# seven_segment_all.net
KiCad netlist of a schematic drawn in EAGLE
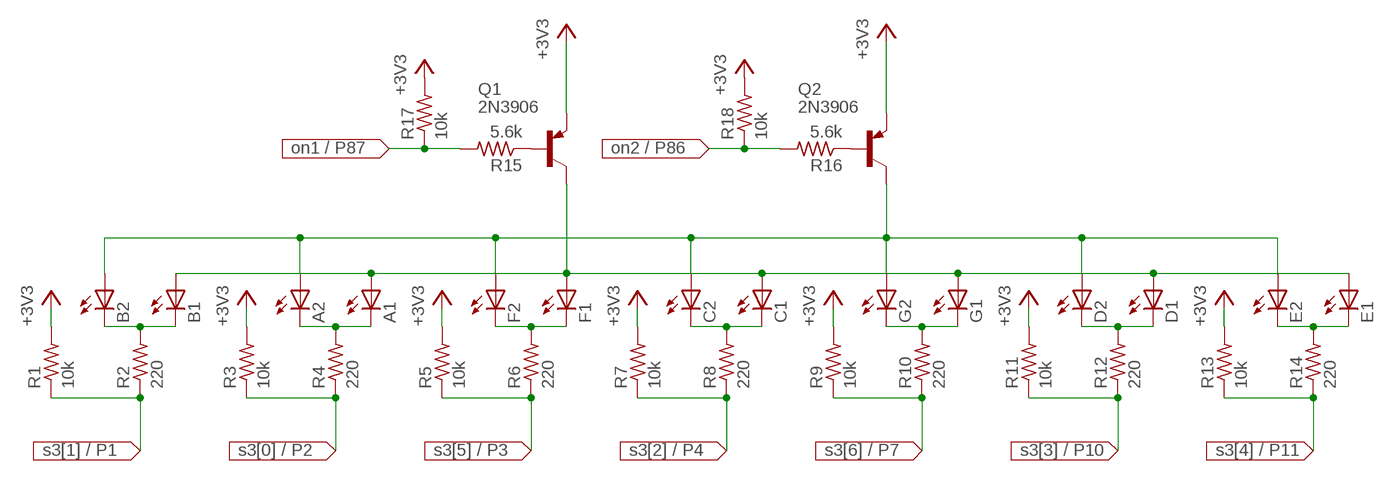
[diagram p0: schematic, sheet 1]

(export (version "E")
  (design (tool "Eeschema 10.0.6"))
  (components
    (comp (ref "A1")
      (value "LED5MM")
      (footprint "eagle-import:LED5MM")
      (libsource (lib "eagle-import") (part "LED5MM"))
    )
    (comp (ref "A2")
      (value "LED5MM")
      (footprint "eagle-import:LED5MM")
      (libsource (lib "eagle-import") (part "LED5MM"))
    )
    (comp (ref "B1")
      (value "LED5MM")
      (footprint "eagle-import:LED5MM")
      (libsource (lib "eagle-import") (part "LED5MM"))
    )
    (comp (ref "B2")
      (value "LED5MM")
      (footprint "eagle-import:LED5MM")
      (libsource (lib "eagle-import") (part "LED5MM"))
    )
    (comp (ref "C1")
      (value "LED5MM")
      (footprint "eagle-import:LED5MM")
      (libsource (lib "eagle-import") (part "LED5MM"))
    )
    (comp (ref "C2")
      (value "LED5MM")
      (footprint "eagle-import:LED5MM")
      (libsource (lib "eagle-import") (part "LED5MM"))
    )
    (comp (ref "D1")
      (value "LED5MM")
      (footprint "eagle-import:LED5MM")
      (libsource (lib "eagle-import") (part "LED5MM"))
    )
    (comp (ref "D2")
      (value "LED5MM")
      (footprint "eagle-import:LED5MM")
      (libsource (lib "eagle-import") (part "LED5MM"))
    )
    (comp (ref "E1")
      (value "LED5MM")
      (footprint "eagle-import:LED5MM")
      (libsource (lib "eagle-import") (part "LED5MM"))
    )
    (comp (ref "E2")
      (value "LED5MM")
      (footprint "eagle-import:LED5MM")
      (libsource (lib "eagle-import") (part "LED5MM"))
    )
    (comp (ref "F1")
      (value "LED5MM")
      (footprint "eagle-import:LED5MM")
      (libsource (lib "eagle-import") (part "LED5MM"))
    )
    (comp (ref "F2")
      (value "LED5MM")
      (footprint "eagle-import:LED5MM")
      (libsource (lib "eagle-import") (part "LED5MM"))
    )
    (comp (ref "G1")
      (value "LED5MM")
      (footprint "eagle-import:LED5MM")
      (libsource (lib "eagle-import") (part "LED5MM"))
    )
    (comp (ref "G2")
      (value "LED5MM")
      (footprint "eagle-import:LED5MM")
      (libsource (lib "eagle-import") (part "LED5MM"))
    )
    (comp (ref "Q1")
      (value "2N3906")
      (footprint "eagle-import:TO92")
      (libsource (lib "eagle-import") (part "2N3906"))
    )
    (comp (ref "Q2")
      (value "2N3906")
      (footprint "eagle-import:TO92")
      (libsource (lib "eagle-import") (part "2N3906"))
    )
    (comp (ref "R1")
      (value "10k")
      (footprint "eagle-import:0411_12")
      (libsource (lib "eagle-import") (part "R-US_0411/12"))
    )
    (comp (ref "R2")
      (value "220")
      (footprint "eagle-import:0411_12")
      (libsource (lib "eagle-import") (part "R-US_0411/12"))
    )
    (comp (ref "R3")
      (value "10k")
      (footprint "eagle-import:0411_12")
      (libsource (lib "eagle-import") (part "R-US_0411/12"))
    )
    (comp (ref "R4")
      (value "220")
      (footprint "eagle-import:0411_12")
      (libsource (lib "eagle-import") (part "R-US_0411/12"))
    )
    (comp (ref "R5")
      (value "10k")
      (footprint "eagle-import:0411_12")
      (libsource (lib "eagle-import") (part "R-US_0411/12"))
    )
    (comp (ref "R6")
      (value "220")
      (footprint "eagle-import:0411_12")
      (libsource (lib "eagle-import") (part "R-US_0411/12"))
    )
    (comp (ref "R7")
      (value "10k")
      (footprint "eagle-import:0411_12")
      (libsource (lib "eagle-import") (part "R-US_0411/12"))
    )
    (comp (ref "R8")
      (value "220")
      (footprint "eagle-import:0411_12")
      (libsource (lib "eagle-import") (part "R-US_0411/12"))
    )
    (comp (ref "R9")
      (value "10k")
      (footprint "eagle-import:0411_12")
      (libsource (lib "eagle-import") (part "R-US_0411/12"))
    )
    (comp (ref "R10")
      (value "220")
      (footprint "eagle-import:0411_12")
      (libsource (lib "eagle-import") (part "R-US_0411/12"))
    )
    (comp (ref "R11")
      (value "10k")
      (footprint "eagle-import:0411_12")
      (libsource (lib "eagle-import") (part "R-US_0411/12"))
    )
    (comp (ref "R12")
      (value "220")
      (footprint "eagle-import:0411_12")
      (libsource (lib "eagle-import") (part "R-US_0411/12"))
    )
    (comp (ref "R13")
      (value "10k")
      (footprint "eagle-import:0411_12")
      (libsource (lib "eagle-import") (part "R-US_0411/12"))
    )
    (comp (ref "R14")
      (value "220")
      (footprint "eagle-import:0411_12")
      (libsource (lib "eagle-import") (part "R-US_0411/12"))
    )
    (comp (ref "R15")
      (value "5.6k")
      (footprint "eagle-import:0411_12")
      (libsource (lib "eagle-import") (part "R-US_0411/12"))
    )
    (comp (ref "R16")
      (value "5.6k")
      (footprint "eagle-import:0411_12")
      (libsource (lib "eagle-import") (part "R-US_0411/12"))
    )
    (comp (ref "R17")
      (value "10k")
      (footprint "eagle-import:0411_12")
      (libsource (lib "eagle-import") (part "R-US_0411/12"))
    )
    (comp (ref "R18")
      (value "10k")
      (footprint "eagle-import:0411_12")
      (libsource (lib "eagle-import") (part "R-US_0411/12"))
    )
  )
  (nets
    (net (code "1") (name "+3V3") (class "Default")
      (node (ref "Q1") (pin "3") (pinfunction "E_3") (pintype "passive"))
      (node (ref "Q2") (pin "3") (pinfunction "E_3") (pintype "passive"))
      (node (ref "R1") (pin "2") (pinfunction "2_2") (pintype "passive"))
      (node (ref "R11") (pin "2") (pinfunction "2_2") (pintype "passive"))
      (node (ref "R13") (pin "2") (pinfunction "2_2") (pintype "passive"))
      (node (ref "R17") (pin "2") (pinfunction "2_2") (pintype "passive"))
      (node (ref "R18") (pin "2") (pinfunction "2_2") (pintype "passive"))
      (node (ref "R3") (pin "2") (pinfunction "2_2") (pintype "passive"))
      (node (ref "R5") (pin "2") (pinfunction "2_2") (pintype "passive"))
      (node (ref "R7") (pin "2") (pinfunction "2_2") (pintype "passive"))
      (node (ref "R9") (pin "2") (pinfunction "2_2") (pintype "passive"))
    )
    (net (code "2") (name "Net-(A1-C)") (class "Default")
      (node (ref "A1") (pin "K") (pinfunction "C_K") (pintype "passive"))
      (node (ref "A2") (pin "K") (pinfunction "C_K") (pintype "passive"))
      (node (ref "R4") (pin "2") (pinfunction "2_2") (pintype "passive"))
    )
    (net (code "3") (name "Net-(B1-C)") (class "Default")
      (node (ref "B1") (pin "K") (pinfunction "C_K") (pintype "passive"))
      (node (ref "B2") (pin "K") (pinfunction "C_K") (pintype "passive"))
      (node (ref "R2") (pin "2") (pinfunction "2_2") (pintype "passive"))
    )
    (net (code "4") (name "Net-(C1-C)") (class "Default")
      (node (ref "C1") (pin "K") (pinfunction "C_K") (pintype "passive"))
      (node (ref "C2") (pin "K") (pinfunction "C_K") (pintype "passive"))
      (node (ref "R8") (pin "2") (pinfunction "2_2") (pintype "passive"))
    )
    (net (code "5") (name "Net-(D1-C)") (class "Default")
      (node (ref "D1") (pin "K") (pinfunction "C_K") (pintype "passive"))
      (node (ref "D2") (pin "K") (pinfunction "C_K") (pintype "passive"))
      (node (ref "R12") (pin "2") (pinfunction "2_2") (pintype "passive"))
    )
    (net (code "6") (name "Net-(E1-C)") (class "Default")
      (node (ref "E1") (pin "K") (pinfunction "C_K") (pintype "passive"))
      (node (ref "E2") (pin "K") (pinfunction "C_K") (pintype "passive"))
      (node (ref "R14") (pin "2") (pinfunction "2_2") (pintype "passive"))
    )
    (net (code "7") (name "Net-(F1-C)") (class "Default")
      (node (ref "F1") (pin "K") (pinfunction "C_K") (pintype "passive"))
      (node (ref "F2") (pin "K") (pinfunction "C_K") (pintype "passive"))
      (node (ref "R6") (pin "2") (pinfunction "2_2") (pintype "passive"))
    )
    (net (code "8") (name "Net-(G1-C)") (class "Default")
      (node (ref "G1") (pin "K") (pinfunction "C_K") (pintype "passive"))
      (node (ref "G2") (pin "K") (pinfunction "C_K") (pintype "passive"))
      (node (ref "R10") (pin "2") (pinfunction "2_2") (pintype "passive"))
    )
    (net (code "9") (name "Net-(Q1-B)") (class "Default")
      (node (ref "Q1") (pin "2") (pinfunction "B_2") (pintype "passive"))
      (node (ref "R15") (pin "1") (pinfunction "1_1") (pintype "passive"))
    )
    (net (code "10") (name "Net-(Q1-C)") (class "Default")
      (node (ref "A1") (pin "A") (pinfunction "A_A") (pintype "passive"))
      (node (ref "B1") (pin "A") (pinfunction "A_A") (pintype "passive"))
      (node (ref "C1") (pin "A") (pinfunction "A_A") (pintype "passive"))
      (node (ref "D1") (pin "A") (pinfunction "A_A") (pintype "passive"))
      (node (ref "E1") (pin "A") (pinfunction "A_A") (pintype "passive"))
      (node (ref "F1") (pin "A") (pinfunction "A_A") (pintype "passive"))
      (node (ref "G1") (pin "A") (pinfunction "A_A") (pintype "passive"))
      (node (ref "Q1") (pin "1") (pinfunction "C_1") (pintype "passive"))
    )
    (net (code "11") (name "Net-(Q2-B)") (class "Default")
      (node (ref "Q2") (pin "2") (pinfunction "B_2") (pintype "passive"))
      (node (ref "R16") (pin "1") (pinfunction "1_1") (pintype "passive"))
    )
    (net (code "12") (name "Net-(Q2-C)") (class "Default")
      (node (ref "A2") (pin "A") (pinfunction "A_A") (pintype "passive"))
      (node (ref "B2") (pin "A") (pinfunction "A_A") (pintype "passive"))
      (node (ref "C2") (pin "A") (pinfunction "A_A") (pintype "passive"))
      (node (ref "D2") (pin "A") (pinfunction "A_A") (pintype "passive"))
      (node (ref "E2") (pin "A") (pinfunction "A_A") (pintype "passive"))
      (node (ref "F2") (pin "A") (pinfunction "A_A") (pintype "passive"))
      (node (ref "G2") (pin "A") (pinfunction "A_A") (pintype "passive"))
      (node (ref "Q2") (pin "1") (pinfunction "C_1") (pintype "passive"))
    )
    (net (code "13") (name "Net-(R1-Pad1)") (class "Default")
      (node (ref "R1") (pin "1") (pinfunction "1_1") (pintype "passive"))
      (node (ref "R2") (pin "1") (pinfunction "1_1") (pintype "passive"))
    )
    (net (code "14") (name "Net-(R3-Pad1)") (class "Default")
      (node (ref "R3") (pin "1") (pinfunction "1_1") (pintype "passive"))
      (node (ref "R4") (pin "1") (pinfunction "1_1") (pintype "passive"))
    )
    (net (code "15") (name "Net-(R5-Pad1)") (class "Default")
      (node (ref "R5") (pin "1") (pinfunction "1_1") (pintype "passive"))
      (node (ref "R6") (pin "1") (pinfunction "1_1") (pintype "passive"))
    )
    (net (code "16") (name "Net-(R7-Pad1)") (class "Default")
      (node (ref "R7") (pin "1") (pinfunction "1_1") (pintype "passive"))
      (node (ref "R8") (pin "1") (pinfunction "1_1") (pintype "passive"))
    )
    (net (code "17") (name "Net-(R10-Pad1)") (class "Default")
      (node (ref "R10") (pin "1") (pinfunction "1_1") (pintype "passive"))
      (node (ref "R9") (pin "1") (pinfunction "1_1") (pintype "passive"))
    )
    (net (code "18") (name "Net-(R11-Pad1)") (class "Default")
      (node (ref "R11") (pin "1") (pinfunction "1_1") (pintype "passive"))
      (node (ref "R12") (pin "1") (pinfunction "1_1") (pintype "passive"))
    )
    (net (code "19") (name "Net-(R13-Pad1)") (class "Default")
      (node (ref "R13") (pin "1") (pinfunction "1_1") (pintype "passive"))
      (node (ref "R14") (pin "1") (pinfunction "1_1") (pintype "passive"))
    )
    (net (code "20") (name "Net-(R15-Pad2)") (class "Default")
      (node (ref "R15") (pin "2") (pinfunction "2_2") (pintype "passive"))
      (node (ref "R17") (pin "1") (pinfunction "1_1") (pintype "passive"))
    )
    (net (code "21") (name "Net-(R16-Pad2)") (class "Default")
      (node (ref "R16") (pin "2") (pinfunction "2_2") (pintype "passive"))
      (node (ref "R18") (pin "1") (pinfunction "1_1") (pintype "passive"))
    )
  )
)
